# INITIAL_DESIGN.net
KiCad netlist of a schematic drawn in EAGLE
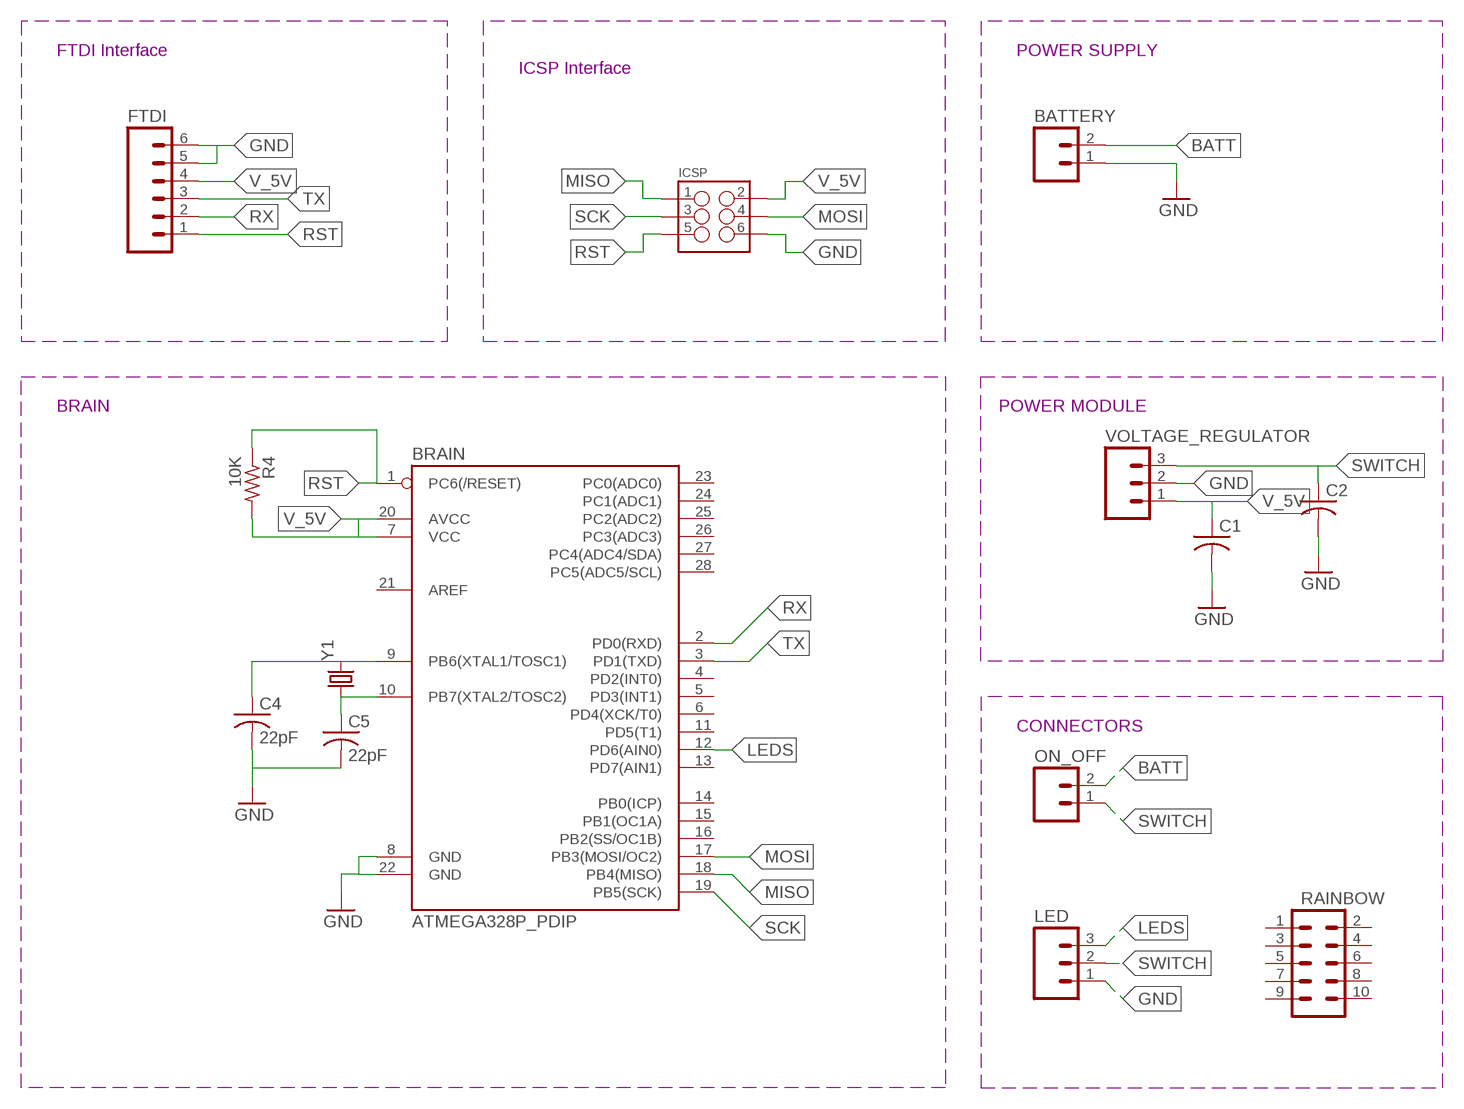
[diagram p0: schematic, sheet 1]

(export (version "E")
  (design (tool "Eeschema 10.0.6"))
  (components
    (comp (ref "BATTERY")
      (value "M02PTH")
      (footprint "eagle-import:1X02")
      (libsource (lib "eagle-import") (part "M02PTH"))
    )
    (comp (ref "BRAIN")
      (value "ATMEGA328P_PDIP")
      (footprint "eagle-import:DIL28-3")
      (libsource (lib "eagle-import") (part "ATMEGA328P_PDIP"))
    )
    (comp (ref "C1")
      (value "C-US025-025X050")
      (footprint "eagle-import:C025-025X050")
      (libsource (lib "eagle-import") (part "C-US025-025X050"))
    )
    (comp (ref "C2")
      (value "C-US025-025X050")
      (footprint "eagle-import:C025-025X050")
      (libsource (lib "eagle-import") (part "C-US025-025X050"))
    )
    (comp (ref "C4")
      (value "22pF")
      (footprint "eagle-import:C025-024X044")
      (libsource (lib "eagle-import") (part "C-US025-024X044"))
    )
    (comp (ref "C5")
      (value "22pF")
      (footprint "eagle-import:C025-024X044")
      (libsource (lib "eagle-import") (part "C-US025-024X044"))
    )
    (comp (ref "FTDI")
      (value "M06POLAR")
      (footprint "eagle-import:MOLEX-1X6")
      (libsource (lib "eagle-import") (part "M06POLAR"))
    )
    (comp (ref "ICSP")
      (value "M03X2SHROUD")
      (footprint "eagle-import:2X3-SHROUDED")
      (libsource (lib "eagle-import") (part "M03X2SHROUD"))
    )
    (comp (ref "LED")
      (value "M03JST-PTH")
      (footprint "eagle-import:JST-3-PTH")
      (libsource (lib "eagle-import") (part "M03JST-PTH"))
    )
    (comp (ref "ON_OFF")
      (value "M02-JST-2-PTH-NO_SILK")
      (footprint "eagle-import:JST-2-PTH-NS")
      (libsource (lib "eagle-import") (part "M02-JST-2-PTH-NO_SILK"))
    )
    (comp (ref "R4")
      (value "10K")
      (footprint "eagle-import:R0805")
      (libsource (lib "eagle-import") (part "R-US_R0805"))
    )
    (comp (ref "RAINBOW")
      (value "M05X2SHD")
      (footprint "eagle-import:2X5-SHROUDED")
      (libsource (lib "eagle-import") (part "M05X2SHD"))
    )
    (comp (ref "VOLTAGE_REGULATOR")
      (value "M03PTH")
      (footprint "eagle-import:1X03")
      (libsource (lib "eagle-import") (part "M03PTH"))
    )
    (comp (ref "Y1")
      (value "CRYSTALHC49US")
      (footprint "eagle-import:HC49US")
      (libsource (lib "eagle-import") (part "CRYSTALHC49US"))
    )
  )
  (nets
    (net (code "1") (name "BATT") (class "Default")
      (node (ref "BATTERY") (pin "2") (pinfunction "2_2") (pintype "passive"))
      (node (ref "ON_OFF") (pin "2") (pinfunction "2_2") (pintype "passive"))
    )
    (net (code "2") (name "GND") (class "Default")
      (node (ref "BATTERY") (pin "1") (pinfunction "1_1") (pintype "passive"))
      (node (ref "BRAIN") (pin "22") (pinfunction "GND_22") (pintype "bidirectional"))
      (node (ref "BRAIN") (pin "8") (pinfunction "GND_8") (pintype "bidirectional"))
      (node (ref "C1") (pin "2") (pinfunction "2_2") (pintype "passive"))
      (node (ref "C2") (pin "2") (pinfunction "2_2") (pintype "passive"))
      (node (ref "C4") (pin "2") (pinfunction "2_2") (pintype "passive"))
      (node (ref "C5") (pin "2") (pinfunction "2_2") (pintype "passive"))
      (node (ref "FTDI") (pin "5") (pinfunction "5_5") (pintype "passive"))
      (node (ref "FTDI") (pin "6") (pinfunction "6_6") (pintype "passive"))
      (node (ref "ICSP") (pin "6") (pinfunction "6_6") (pintype "bidirectional"))
      (node (ref "LED") (pin "1") (pinfunction "1_1") (pintype "passive"))
      (node (ref "VOLTAGE_REGULATOR") (pin "2") (pinfunction "2_2") (pintype "passive"))
    )
    (net (code "3") (name "LEDS") (class "Default")
      (node (ref "BRAIN") (pin "12") (pinfunction "PD6(AIN0)_12") (pintype "bidirectional"))
      (node (ref "LED") (pin "3") (pinfunction "3_3") (pintype "passive"))
    )
    (net (code "4") (name "MISO") (class "Default")
      (node (ref "BRAIN") (pin "18") (pinfunction "PB4(MISO)_18") (pintype "bidirectional"))
      (node (ref "ICSP") (pin "1") (pinfunction "1_1") (pintype "bidirectional"))
    )
    (net (code "5") (name "MOSI") (class "Default")
      (node (ref "BRAIN") (pin "17") (pinfunction "PB3(MOSI/OC2)_17") (pintype "bidirectional"))
      (node (ref "ICSP") (pin "4") (pinfunction "4_4") (pintype "bidirectional"))
    )
    (net (code "6") (name "Net-(BRAIN-PB6(XTAL1{slash}TOSC1))") (class "Default")
      (node (ref "BRAIN") (pin "9") (pinfunction "PB6(XTAL1/TOSC1)_9") (pintype "bidirectional"))
      (node (ref "C4") (pin "1") (pinfunction "1_1") (pintype "passive"))
      (node (ref "Y1") (pin "2") (pinfunction "2_2") (pintype "passive"))
    )
    (net (code "7") (name "Net-(BRAIN-PB7(XTAL2{slash}TOSC2))") (class "Default")
      (node (ref "BRAIN") (pin "10") (pinfunction "PB7(XTAL2/TOSC2)_10") (pintype "bidirectional"))
      (node (ref "C5") (pin "1") (pinfunction "1_1") (pintype "passive"))
      (node (ref "Y1") (pin "1") (pinfunction "1_1") (pintype "passive"))
    )
    (net (code "8") (name "RST") (class "Default")
      (node (ref "BRAIN") (pin "1") (pinfunction "PC6(/RESET)_1") (pintype "bidirectional"))
      (node (ref "FTDI") (pin "1") (pinfunction "1_1") (pintype "passive"))
      (node (ref "ICSP") (pin "5") (pinfunction "5_5") (pintype "bidirectional"))
      (node (ref "R4") (pin "1") (pinfunction "1_1") (pintype "passive"))
    )
    (net (code "9") (name "RX") (class "Default")
      (node (ref "BRAIN") (pin "2") (pinfunction "PD0(RXD)_2") (pintype "bidirectional"))
      (node (ref "FTDI") (pin "2") (pinfunction "2_2") (pintype "passive"))
    )
    (net (code "10") (name "SCK") (class "Default")
      (node (ref "BRAIN") (pin "19") (pinfunction "PB5(SCK)_19") (pintype "bidirectional"))
      (node (ref "ICSP") (pin "3") (pinfunction "3_3") (pintype "bidirectional"))
    )
    (net (code "11") (name "SWITCH") (class "Default")
      (node (ref "C2") (pin "1") (pinfunction "1_1") (pintype "passive"))
      (node (ref "LED") (pin "2") (pinfunction "2_2") (pintype "passive"))
      (node (ref "ON_OFF") (pin "1") (pinfunction "1_1") (pintype "passive"))
      (node (ref "VOLTAGE_REGULATOR") (pin "3") (pinfunction "3_3") (pintype "passive"))
    )
    (net (code "12") (name "TX") (class "Default")
      (node (ref "BRAIN") (pin "3") (pinfunction "PD1(TXD)_3") (pintype "bidirectional"))
      (node (ref "FTDI") (pin "3") (pinfunction "3_3") (pintype "passive"))
    )
    (net (code "13") (name "V_5V") (class "Default")
      (node (ref "BRAIN") (pin "20") (pinfunction "AVCC_20") (pintype "bidirectional"))
      (node (ref "BRAIN") (pin "7") (pinfunction "VCC_7") (pintype "bidirectional"))
      (node (ref "C1") (pin "1") (pinfunction "1_1") (pintype "passive"))
      (node (ref "FTDI") (pin "4") (pinfunction "4_4") (pintype "passive"))
      (node (ref "ICSP") (pin "2") (pinfunction "2_2") (pintype "bidirectional"))
      (node (ref "R4") (pin "2") (pinfunction "2_2") (pintype "passive"))
      (node (ref "VOLTAGE_REGULATOR") (pin "1") (pinfunction "1_1") (pintype "passive"))
    )
    (net (code "14") (name "unconnected-(BRAIN-AREF-Pad21)") (class "Default")
      (node (ref "BRAIN") (pin "21") (pinfunction "AREF_21") (pintype "bidirectional"))
    )
    (net (code "15") (name "unconnected-(BRAIN-PB0(ICP)-Pad14)") (class "Default")
      (node (ref "BRAIN") (pin "14") (pinfunction "PB0(ICP)_14") (pintype "bidirectional"))
    )
    (net (code "16") (name "unconnected-(BRAIN-PB1(OC1A)-Pad15)") (class "Default")
      (node (ref "BRAIN") (pin "15") (pinfunction "PB1(OC1A)_15") (pintype "bidirectional"))
    )
    (net (code "17") (name "unconnected-(BRAIN-PB2(SS{slash}OC1B)-Pad16)") (class "Default")
      (node (ref "BRAIN") (pin "16") (pinfunction "PB2(SS/OC1B)_16") (pintype "bidirectional"))
    )
    (net (code "18") (name "unconnected-(BRAIN-PC0(ADC0)-Pad23)") (class "Default")
      (node (ref "BRAIN") (pin "23") (pinfunction "PC0(ADC0)_23") (pintype "bidirectional"))
    )
    (net (code "19") (name "unconnected-(BRAIN-PC1(ADC1)-Pad24)") (class "Default")
      (node (ref "BRAIN") (pin "24") (pinfunction "PC1(ADC1)_24") (pintype "bidirectional"))
    )
    (net (code "20") (name "unconnected-(BRAIN-PC2(ADC2)-Pad25)") (class "Default")
      (node (ref "BRAIN") (pin "25") (pinfunction "PC2(ADC2)_25") (pintype "bidirectional"))
    )
    (net (code "21") (name "unconnected-(BRAIN-PC3(ADC3)-Pad26)") (class "Default")
      (node (ref "BRAIN") (pin "26") (pinfunction "PC3(ADC3)_26") (pintype "bidirectional"))
    )
    (net (code "22") (name "unconnected-(BRAIN-PC4(ADC4{slash}SDA)-Pad27)") (class "Default")
      (node (ref "BRAIN") (pin "27") (pinfunction "PC4(ADC4/SDA)_27") (pintype "bidirectional"))
    )
    (net (code "23") (name "unconnected-(BRAIN-PC5(ADC5{slash}SCL)-Pad28)") (class "Default")
      (node (ref "BRAIN") (pin "28") (pinfunction "PC5(ADC5/SCL)_28") (pintype "bidirectional"))
    )
    (net (code "24") (name "unconnected-(BRAIN-PD2(INT0)-Pad4)") (class "Default")
      (node (ref "BRAIN") (pin "4") (pinfunction "PD2(INT0)_4") (pintype "bidirectional"))
    )
    (net (code "25") (name "unconnected-(BRAIN-PD3(INT1)-Pad5)") (class "Default")
      (node (ref "BRAIN") (pin "5") (pinfunction "PD3(INT1)_5") (pintype "bidirectional"))
    )
    (net (code "26") (name "unconnected-(BRAIN-PD4(XCK{slash}T0)-Pad6)") (class "Default")
      (node (ref "BRAIN") (pin "6") (pinfunction "PD4(XCK/T0)_6") (pintype "bidirectional"))
    )
    (net (code "27") (name "unconnected-(BRAIN-PD5(T1)-Pad11)") (class "Default")
      (node (ref "BRAIN") (pin "11") (pinfunction "PD5(T1)_11") (pintype "bidirectional"))
    )
    (net (code "28") (name "unconnected-(BRAIN-PD7(AIN1)-Pad13)") (class "Default")
      (node (ref "BRAIN") (pin "13") (pinfunction "PD7(AIN1)_13") (pintype "bidirectional"))
    )
    (net (code "29") (name "unconnected-(RAINBOW-Pad1)") (class "Default")
      (node (ref "RAINBOW") (pin "1") (pinfunction "1_1") (pintype "passive"))
    )
    (net (code "30") (name "unconnected-(RAINBOW-Pad2)") (class "Default")
      (node (ref "RAINBOW") (pin "2") (pinfunction "2_2") (pintype "passive"))
    )
    (net (code "31") (name "unconnected-(RAINBOW-Pad3)") (class "Default")
      (node (ref "RAINBOW") (pin "3") (pinfunction "3_3") (pintype "passive"))
    )
    (net (code "32") (name "unconnected-(RAINBOW-Pad4)") (class "Default")
      (node (ref "RAINBOW") (pin "4") (pinfunction "4_4") (pintype "passive"))
    )
    (net (code "33") (name "unconnected-(RAINBOW-Pad5)") (class "Default")
      (node (ref "RAINBOW") (pin "5") (pinfunction "5_5") (pintype "passive"))
    )
    (net (code "34") (name "unconnected-(RAINBOW-Pad6)") (class "Default")
      (node (ref "RAINBOW") (pin "6") (pinfunction "6_6") (pintype "passive"))
    )
    (net (code "35") (name "unconnected-(RAINBOW-Pad7)") (class "Default")
      (node (ref "RAINBOW") (pin "7") (pinfunction "7_7") (pintype "passive"))
    )
    (net (code "36") (name "unconnected-(RAINBOW-Pad8)") (class "Default")
      (node (ref "RAINBOW") (pin "8") (pinfunction "8_8") (pintype "passive"))
    )
    (net (code "37") (name "unconnected-(RAINBOW-Pad9)") (class "Default")
      (node (ref "RAINBOW") (pin "9") (pinfunction "9_9") (pintype "passive"))
    )
    (net (code "38") (name "unconnected-(RAINBOW-Pad10)") (class "Default")
      (node (ref "RAINBOW") (pin "10") (pinfunction "10_10") (pintype "passive"))
    )
  )
)
